# IMU_standalone.net
KiCad netlist of a schematic drawn in Altium Designer
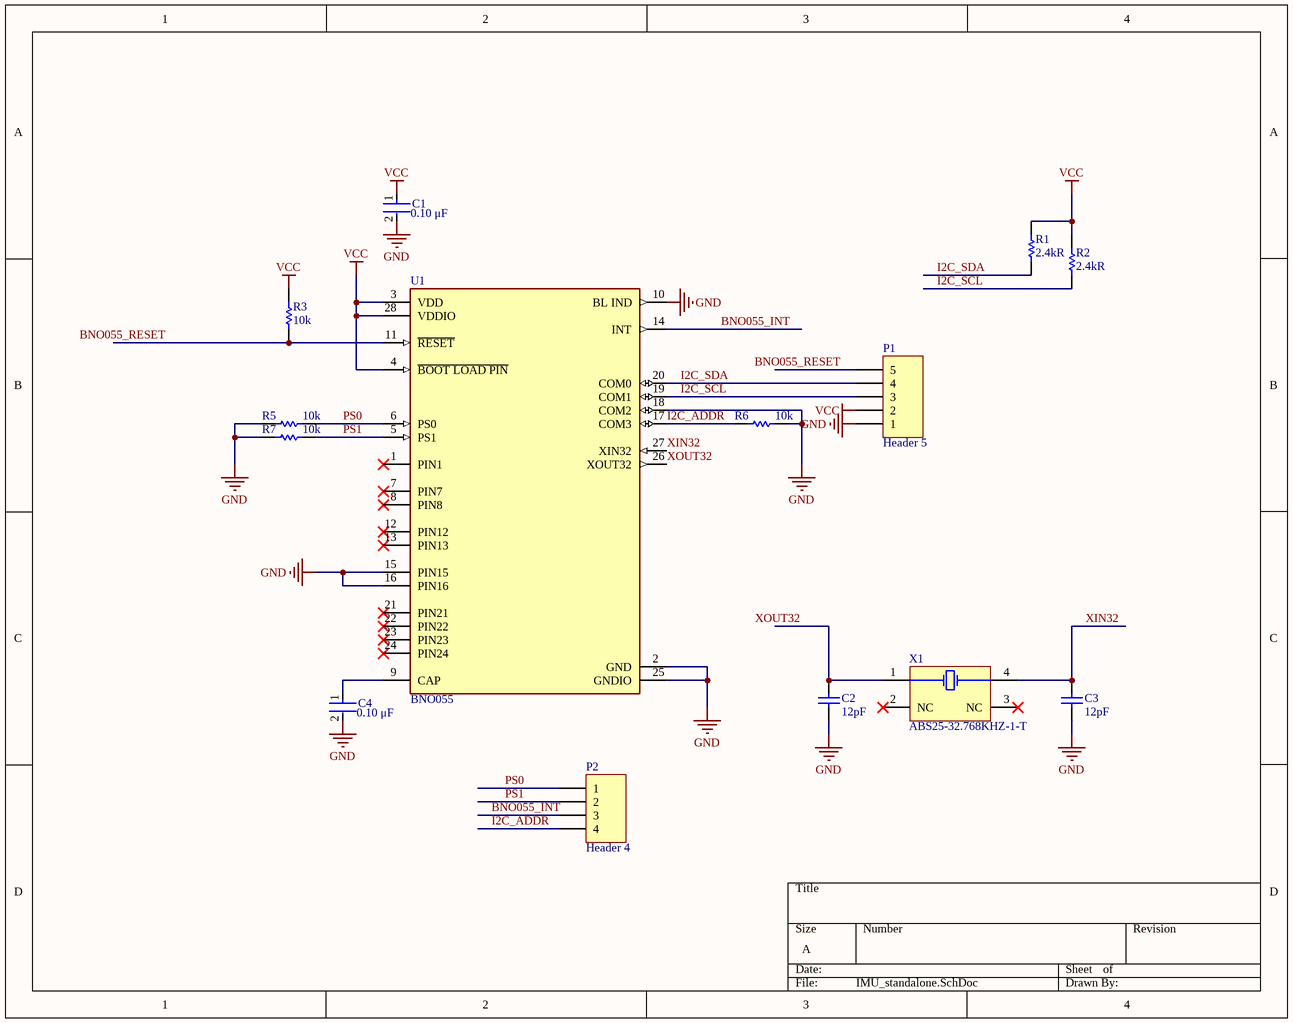
[diagram p0: IMU_standalone.SchDoc]

(export (version "E")
  (design (tool "Eeschema 10.0.6"))
  (components
    (comp (ref "C1")
      (value "C0603_0.1UF")
      (footprint "FP-C0603C-CF-MFG")
      (description "CAP CER 0.1UF 16V X7R 0603")
      (fields
        (field (name "TOLERANCE") "0.2")
        (field (name "CAPACITANCE") "0.10 μF")
        (field (name "MANUFACTURER PART NUMBER") "C0603C104M4RAC7411")
      )
      (libsource (lib "Altium Content Vault") (part "b4654b650e69147ec39a6b967a45e02"))
    )
    (comp (ref "C2")
      (value "12pF")
      (footprint "CAPC1608X90X40NL10T20")
      (description "Chip Capacitor, 12 pF, +/- 5%, 50 V, -55 to 125 degC, 0603 (1608 Metric), RoHS, Tape and Reel")
      (fields (field (name "TOLERANCE") "1%") (field (name "Comment") "C0603_12PF"))
      (libsource (lib "Altium Content Vault") (part "CAP-NP-2"))
    )
    (comp (ref "C3")
      (value "12pF")
      (footprint "CAPC1608X90X40NL10T20")
      (description "Chip Capacitor, 12 pF, +/- 5%, 50 V, -55 to 125 degC, 0603 (1608 Metric), RoHS, Tape and Reel")
      (fields (field (name "TOLERANCE") "1%") (field (name "Comment") "C0603_12PF"))
      (libsource (lib "Altium Content Vault") (part "CAP-NP-2"))
    )
    (comp (ref "C4")
      (value "C0603_0.1UF")
      (footprint "FP-C0603C-CF-MFG")
      (description "CAP CER 0.1UF 16V X7R 0603")
      (fields
        (field (name "TOLERANCE") "0.2")
        (field (name "CAPACITANCE") "0.10 μF")
        (field (name "MANUFACTURER PART NUMBER") "C0603C104M4RAC7411")
      )
      (libsource (lib "Altium Content Vault") (part "b4654b650e69147ec39a6b967a45e02"))
    )
    (comp (ref "P1")
      (value "Header 5")
      (footprint "HDR1X5")
      (description "Header, 5-Pin")
      (fields (field (name "PUBLISHER") "Altium Limited"))
      (libsource (lib "Miscellaneous Connectors") (part "Header 5"))
    )
    (comp (ref "P2")
      (value "Header 4")
      (footprint "HDR1X4")
      (description "Header, 4-Pin")
      (fields (field (name "PUBLISHER") "Altium Limited"))
      (libsource (lib "Miscellaneous Connectors") (part "Header 4"))
    )
    (comp (ref "R1")
      (value "2.4kR")
      (footprint "RESC1608X50X30ML20T20")
      (fields
        (field (name "PART NUMBER") "RR0816P-242-D")
        (field (name "MANUFACTURER") "Susumu")
        (field (name "Comment") "R0603_2.4K")
      )
      (libsource (lib "Altium Content Vault") (part "RES"))
    )
    (comp (ref "R2")
      (value "2.4kR")
      (footprint "RESC1608X50X30ML20T20")
      (fields
        (field (name "PART NUMBER") "RR0816P-242-D")
        (field (name "MANUFACTURER") "Susumu")
        (field (name "Comment") "R0603_2.4K")
      )
      (libsource (lib "Altium Content Vault") (part "RES"))
    )
    (comp (ref "R3")
      (value "10k")
      (footprint "RESC1609X55X30LL15T15")
      (description "Chip Resistor, 10 KOhm, +/- 1%, 0.1 W, -55 to 155 degC, 0603 (1608 Metric), RoHS, Tape and Reel")
      (fields (field (name "TOLERANCE") "1%") (field (name "MANUFACTURER") "Panasonic"))
      (libsource (lib "Altium Content Vault") (part "RES-2"))
    )
    (comp (ref "R5")
      (value "10k")
      (footprint "RESC1609X55X30LL15T15")
      (description "Chip Resistor, 10 KOhm, +/- 1%, 0.1 W, -55 to 155 degC, 0603 (1608 Metric), RoHS, Tape and Reel")
      (fields (field (name "TOLERANCE") "1%") (field (name "MANUFACTURER") "Panasonic"))
      (libsource (lib "Altium Content Vault") (part "RES-2"))
    )
    (comp (ref "R6")
      (value "10k")
      (footprint "RESC1609X55X30LL15T15")
      (description "Chip Resistor, 10 KOhm, +/- 1%, 0.1 W, -55 to 155 degC, 0603 (1608 Metric), RoHS, Tape and Reel")
      (fields (field (name "TOLERANCE") "1%") (field (name "MANUFACTURER") "Panasonic"))
      (libsource (lib "Altium Content Vault") (part "RES-2"))
    )
    (comp (ref "R7")
      (value "10k")
      (footprint "RESC1609X55X30LL15T15")
      (description "Chip Resistor, 10 KOhm, +/- 1%, 0.1 W, -55 to 155 degC, 0603 (1608 Metric), RoHS, Tape and Reel")
      (fields (field (name "TOLERANCE") "1%") (field (name "MANUFACTURER") "Panasonic"))
      (libsource (lib "Altium Content Vault") (part "RES-2"))
    )
    (comp (ref "U1")
      (value "BNO055")
      (footprint "FP-BNO055-MFG")
      (description "IMU ACCEL/GYRO/MAG I2C 28LGA")
      (fields
        (field (name "OCTOPART") "https://octopart.com/bno055-bosch+sensortec-50309911")
        (field (name "VOLTAGE") "1.7~3.6V")
      )
      (libsource (lib "Finger_module") (part "CMP-191067-000002-1"))
    )
    (comp (ref "X1")
      (value "ABS25-32.768KHZ-1-T")
      (footprint "ABRA-ABS25-4_V")
      (description "Low Frequency Crystal, 32.768 KHz, -40 to 85 degC, 4-Pin SMD, RoHS, Tape and Reel")
      (fields (field (name "MANUFACTURER") "ABRACON") (field (name "TOLERANCE") "10PPM"))
      (libsource (lib "Altium Content Vault") (part "XTAL-1-4-4_A"))
    )
  )
  (nets
    (net (code "1") (name "/BNO055_INT") (class "Default")
      (node (ref "P2") (pin "3") (pinfunction "3_3") (pintype "passive"))
      (node (ref "U1") (pin "14") (pinfunction "INT_14") (pintype "output"))
    )
    (net (code "2") (name "/BNO055_RESET") (class "Default")
      (node (ref "P1") (pin "5") (pinfunction "5_5") (pintype "passive"))
      (node (ref "R3") (pin "1") (pinfunction "1_1") (pintype "passive"))
      (node (ref "U1") (pin "11") (pinfunction "~{RESET}_11") (pintype "input"))
    )
    (net (code "3") (name "/I2C_ADDR") (class "Default")
      (node (ref "P2") (pin "4") (pinfunction "4_4") (pintype "passive"))
      (node (ref "R6") (pin "2") (pinfunction "2_2") (pintype "passive"))
      (node (ref "U1") (pin "17") (pinfunction "COM3_17") (pintype "bidirectional"))
    )
    (net (code "4") (name "/I2C_SCL") (class "Default")
      (node (ref "P1") (pin "3") (pinfunction "3_3") (pintype "passive"))
      (node (ref "R2") (pin "1") (pinfunction "1_1") (pintype "passive"))
      (node (ref "U1") (pin "19") (pinfunction "COM1_19") (pintype "bidirectional"))
    )
    (net (code "5") (name "/I2C_SDA") (class "Default")
      (node (ref "P1") (pin "4") (pinfunction "4_4") (pintype "passive"))
      (node (ref "R1") (pin "1") (pinfunction "1_1") (pintype "passive"))
      (node (ref "U1") (pin "20") (pinfunction "COM0_20") (pintype "bidirectional"))
    )
    (net (code "6") (name "/PS0") (class "Default")
      (node (ref "P2") (pin "1") (pinfunction "1_1") (pintype "passive"))
      (node (ref "R5") (pin "2") (pinfunction "2_2") (pintype "passive"))
      (node (ref "U1") (pin "6") (pinfunction "PS0_6") (pintype "input"))
    )
    (net (code "7") (name "/PS1") (class "Default")
      (node (ref "P2") (pin "2") (pinfunction "2_2") (pintype "passive"))
      (node (ref "R7") (pin "2") (pinfunction "2_2") (pintype "passive"))
      (node (ref "U1") (pin "5") (pinfunction "PS1_5") (pintype "input"))
    )
    (net (code "8") (name "/XIN32") (class "Default")
      (node (ref "C3") (pin "2") (pinfunction "2_2") (pintype "passive"))
      (node (ref "U1") (pin "27") (pinfunction "XIN32_27") (pintype "input"))
      (node (ref "X1") (pin "4") (pinfunction "X2_4") (pintype "passive"))
    )
    (net (code "9") (name "/XOUT32") (class "Default")
      (node (ref "C2") (pin "2") (pinfunction "2_2") (pintype "passive"))
      (node (ref "U1") (pin "26") (pinfunction "XOUT32_26") (pintype "output"))
      (node (ref "X1") (pin "1") (pinfunction "X1_1") (pintype "passive"))
    )
    (net (code "10") (name "GND") (class "Default")
      (node (ref "C1") (pin "2") (pinfunction "2_2") (pintype "passive"))
      (node (ref "C2") (pin "1") (pinfunction "1_1") (pintype "passive"))
      (node (ref "C3") (pin "1") (pinfunction "1_1") (pintype "passive"))
      (node (ref "C4") (pin "2") (pinfunction "2_2") (pintype "passive"))
      (node (ref "P1") (pin "1") (pinfunction "1_1") (pintype "passive"))
      (node (ref "R5") (pin "1") (pinfunction "1_1") (pintype "passive"))
      (node (ref "R6") (pin "1") (pinfunction "1_1") (pintype "passive"))
      (node (ref "R7") (pin "1") (pinfunction "1_1") (pintype "passive"))
      (node (ref "U1") (pin "10") (pinfunction "BL_IND_10") (pintype "output"))
      (node (ref "U1") (pin "15") (pinfunction "PIN15_15") (pintype "power_in"))
      (node (ref "U1") (pin "16") (pinfunction "PIN16_16") (pintype "power_in"))
      (node (ref "U1") (pin "18") (pinfunction "COM2_18") (pintype "bidirectional"))
      (node (ref "U1") (pin "2") (pinfunction "GND_2") (pintype "power_in"))
      (node (ref "U1") (pin "25") (pinfunction "GNDIO_25") (pintype "power_in"))
    )
    (net (code "11") (name "Net-(U1-CAP)") (class "Default")
      (node (ref "C4") (pin "1") (pinfunction "1_1") (pintype "passive"))
      (node (ref "U1") (pin "9") (pinfunction "CAP_9") (pintype "passive"))
    )
    (net (code "12") (name "VCC") (class "Default")
      (node (ref "C1") (pin "1") (pinfunction "1_1") (pintype "passive"))
      (node (ref "P1") (pin "2") (pinfunction "2_2") (pintype "passive"))
      (node (ref "R1") (pin "2") (pinfunction "2_2") (pintype "passive"))
      (node (ref "R2") (pin "2") (pinfunction "2_2") (pintype "passive"))
      (node (ref "R3") (pin "2") (pinfunction "2_2") (pintype "passive"))
      (node (ref "U1") (pin "28") (pinfunction "VDDIO_28") (pintype "power_in"))
      (node (ref "U1") (pin "3") (pinfunction "VDD_3") (pintype "power_in"))
      (node (ref "U1") (pin "4") (pinfunction "~{BOOT_LOAD_PIN}_4") (pintype "input"))
    )
    (net (code "13") (name "unconnected-(U1-PIN1-Pad1)") (class "Default")
      (node (ref "U1") (pin "1") (pinfunction "PIN1_1") (pintype "passive+no_connect"))
    )
    (net (code "14") (name "unconnected-(U1-PIN7-Pad7)") (class "Default")
      (node (ref "U1") (pin "7") (pinfunction "PIN7_7") (pintype "passive+no_connect"))
    )
    (net (code "15") (name "unconnected-(U1-PIN8-Pad8)") (class "Default")
      (node (ref "U1") (pin "8") (pinfunction "PIN8_8") (pintype "passive+no_connect"))
    )
    (net (code "16") (name "unconnected-(U1-PIN12-Pad12)") (class "Default")
      (node (ref "U1") (pin "12") (pinfunction "PIN12_12") (pintype "passive+no_connect"))
    )
    (net (code "17") (name "unconnected-(U1-PIN13-Pad13)") (class "Default")
      (node (ref "U1") (pin "13") (pinfunction "PIN13_13") (pintype "passive+no_connect"))
    )
    (net (code "18") (name "unconnected-(U1-PIN21-Pad21)") (class "Default")
      (node (ref "U1") (pin "21") (pinfunction "PIN21_21") (pintype "passive+no_connect"))
    )
    (net (code "19") (name "unconnected-(U1-PIN22-Pad22)") (class "Default")
      (node (ref "U1") (pin "22") (pinfunction "PIN22_22") (pintype "passive+no_connect"))
    )
    (net (code "20") (name "unconnected-(U1-PIN23-Pad23)") (class "Default")
      (node (ref "U1") (pin "23") (pinfunction "PIN23_23") (pintype "passive+no_connect"))
    )
    (net (code "21") (name "unconnected-(U1-PIN24-Pad24)") (class "Default")
      (node (ref "U1") (pin "24") (pinfunction "PIN24_24") (pintype "passive+no_connect"))
    )
    (net (code "22") (name "unconnected-(X1-NC-Pad2)") (class "Default")
      (node (ref "X1") (pin "2") (pinfunction "NC_2") (pintype "passive+no_connect"))
    )
    (net (code "23") (name "unconnected-(X1-NC-Pad3)") (class "Default")
      (node (ref "X1") (pin "3") (pinfunction "NC_3") (pintype "passive+no_connect"))
    )
  )
)
